# EscapeRoom_Shield_Mega_Master.net
KiCad netlist of a schematic drawn in EAGLE
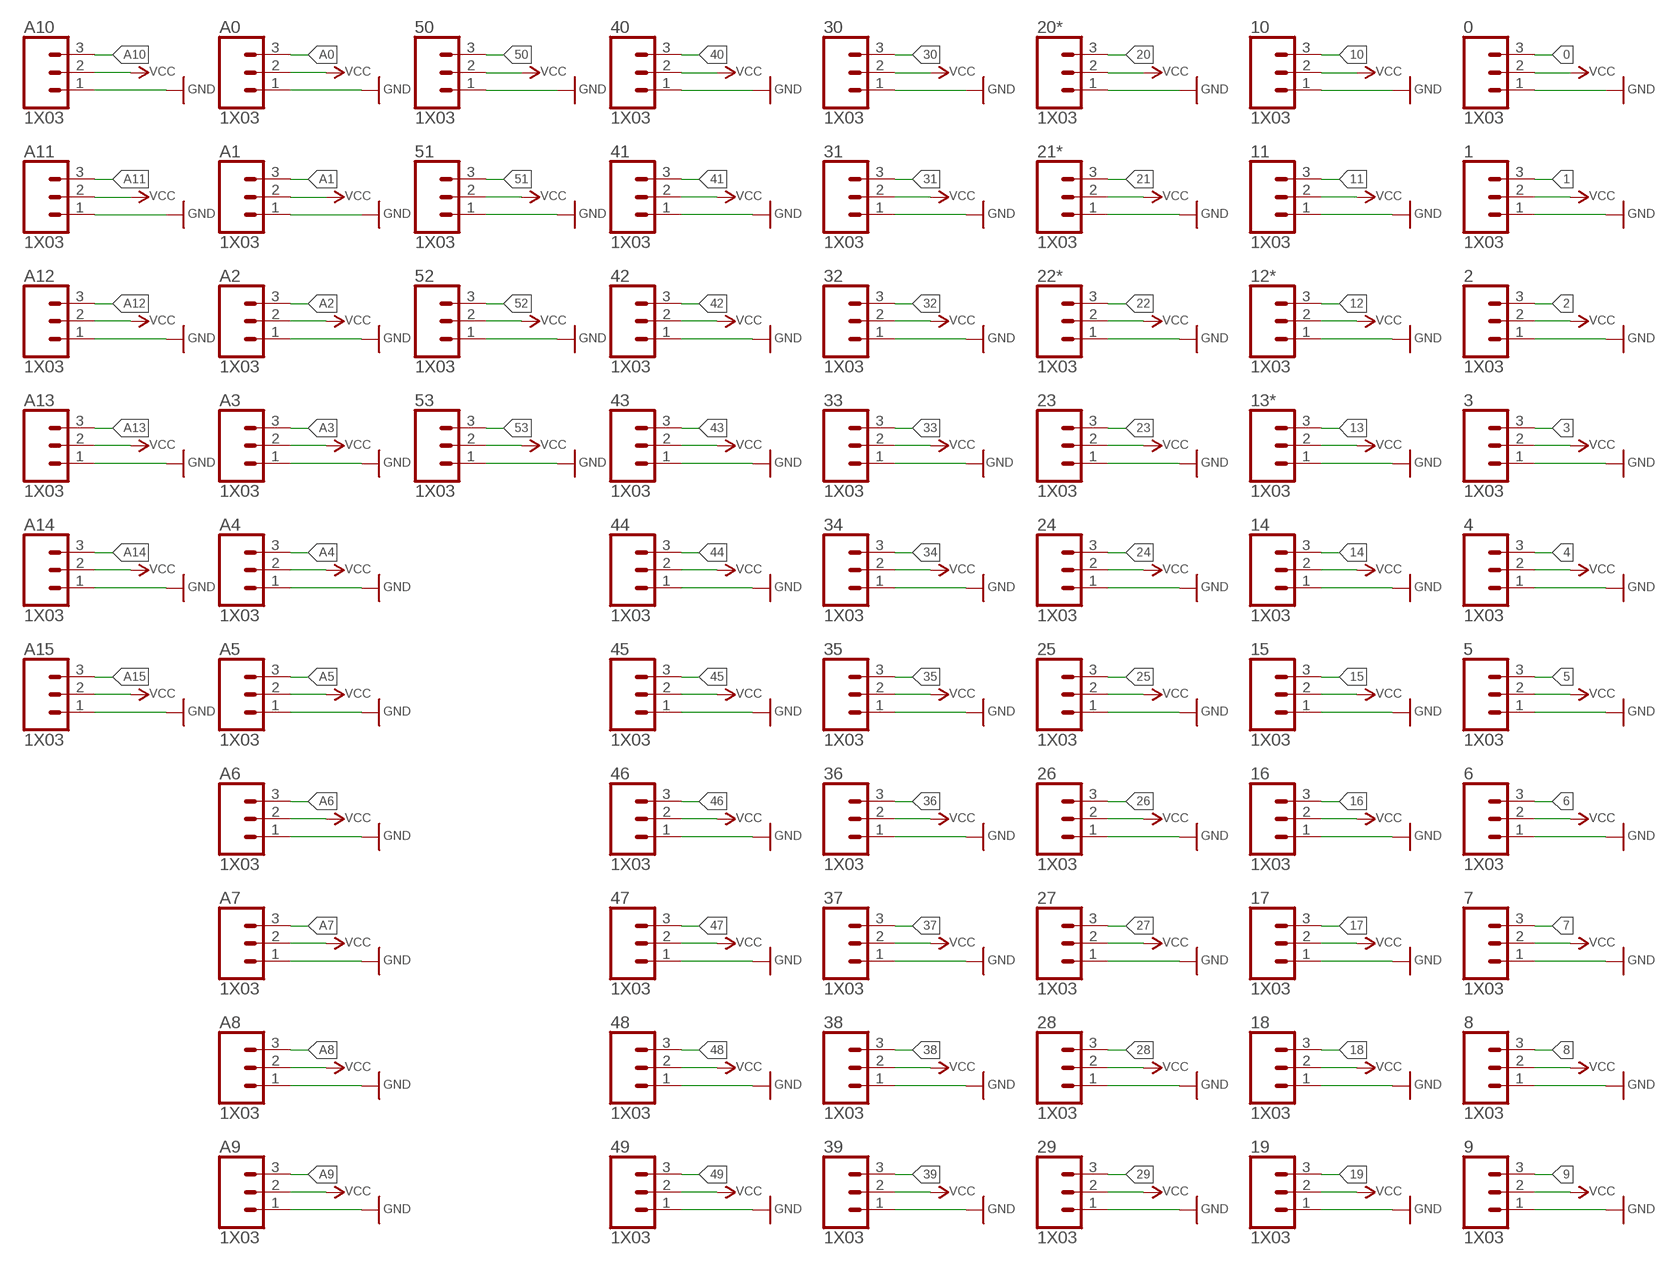
[diagram p0: schematic, sheet 1, part 1 of 2]
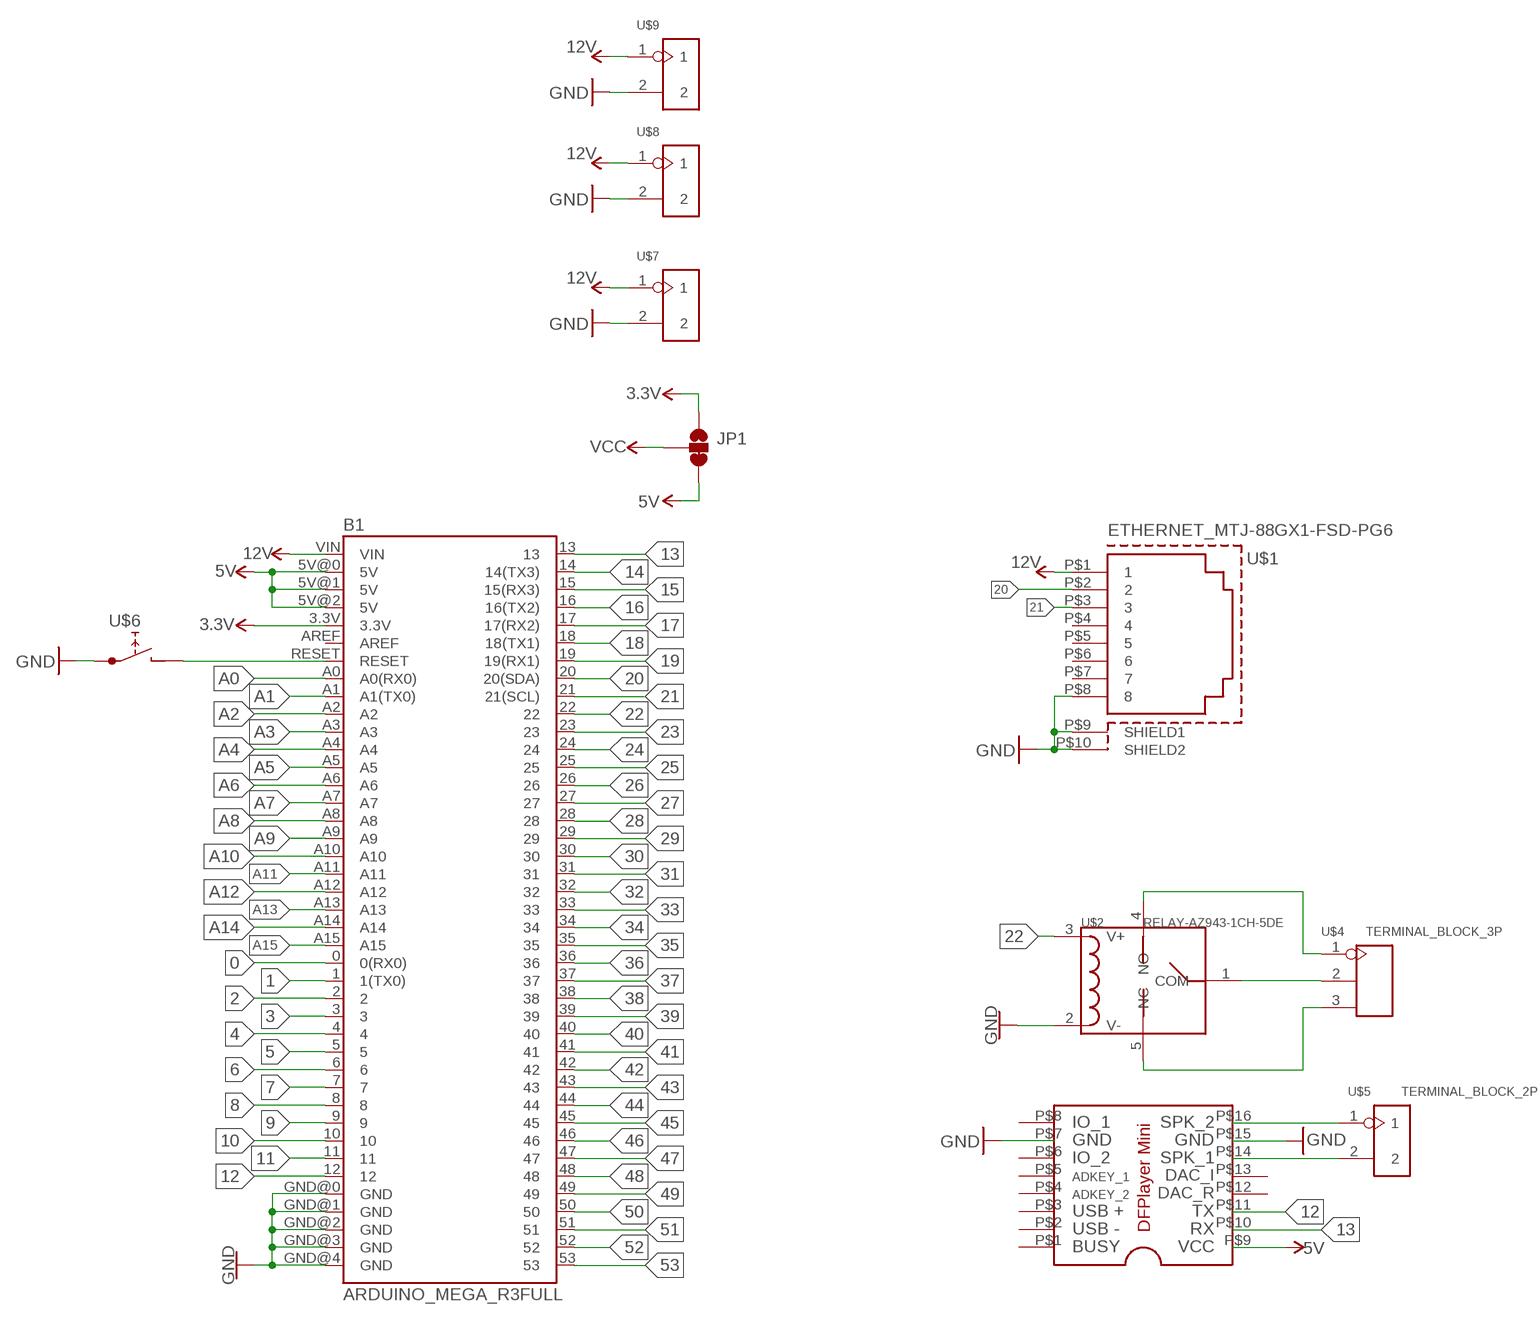
[diagram p1: schematic, sheet 1, part 2 of 2]

(export (version "E")
  (design (tool "Eeschema 10.0.6"))
  (components
    (comp (ref "0")
      (value "1X03")
      (footprint "eagle-import:1X03")
      (libsource (lib "eagle-import") (part "1X03"))
    )
    (comp (ref "1")
      (value "1X03")
      (footprint "eagle-import:1X03")
      (libsource (lib "eagle-import") (part "1X03"))
    )
    (comp (ref "2")
      (value "1X03")
      (footprint "eagle-import:1X03")
      (libsource (lib "eagle-import") (part "1X03"))
    )
    (comp (ref "3")
      (value "1X03")
      (footprint "eagle-import:1X03")
      (libsource (lib "eagle-import") (part "1X03"))
    )
    (comp (ref "4")
      (value "1X03")
      (footprint "eagle-import:1X03")
      (libsource (lib "eagle-import") (part "1X03"))
    )
    (comp (ref "5")
      (value "1X03")
      (footprint "eagle-import:1X03")
      (libsource (lib "eagle-import") (part "1X03"))
    )
    (comp (ref "6")
      (value "1X03")
      (footprint "eagle-import:1X03")
      (libsource (lib "eagle-import") (part "1X03"))
    )
    (comp (ref "7")
      (value "1X03")
      (footprint "eagle-import:1X03")
      (libsource (lib "eagle-import") (part "1X03"))
    )
    (comp (ref "8")
      (value "1X03")
      (footprint "eagle-import:1X03")
      (libsource (lib "eagle-import") (part "1X03"))
    )
    (comp (ref "9")
      (value "1X03")
      (footprint "eagle-import:1X03")
      (libsource (lib "eagle-import") (part "1X03"))
    )
    (comp (ref "10")
      (value "1X03")
      (footprint "eagle-import:1X03")
      (libsource (lib "eagle-import") (part "1X03"))
    )
    (comp (ref "11")
      (value "1X03")
      (footprint "eagle-import:1X03")
      (libsource (lib "eagle-import") (part "1X03"))
    )
    (comp (ref "12*")
      (value "1X03")
      (footprint "eagle-import:1X03")
      (libsource (lib "eagle-import") (part "1X03"))
    )
    (comp (ref "13*")
      (value "1X03")
      (footprint "eagle-import:1X03")
      (libsource (lib "eagle-import") (part "1X03"))
    )
    (comp (ref "14")
      (value "1X03")
      (footprint "eagle-import:1X03")
      (libsource (lib "eagle-import") (part "1X03"))
    )
    (comp (ref "15")
      (value "1X03")
      (footprint "eagle-import:1X03")
      (libsource (lib "eagle-import") (part "1X03"))
    )
    (comp (ref "16")
      (value "1X03")
      (footprint "eagle-import:1X03")
      (libsource (lib "eagle-import") (part "1X03"))
    )
    (comp (ref "17")
      (value "1X03")
      (footprint "eagle-import:1X03")
      (libsource (lib "eagle-import") (part "1X03"))
    )
    (comp (ref "18")
      (value "1X03")
      (footprint "eagle-import:1X03")
      (libsource (lib "eagle-import") (part "1X03"))
    )
    (comp (ref "19")
      (value "1X03")
      (footprint "eagle-import:1X03")
      (libsource (lib "eagle-import") (part "1X03"))
    )
    (comp (ref "20*")
      (value "1X03")
      (footprint "eagle-import:1X03")
      (libsource (lib "eagle-import") (part "1X03"))
    )
    (comp (ref "21*")
      (value "1X03")
      (footprint "eagle-import:1X03")
      (libsource (lib "eagle-import") (part "1X03"))
    )
    (comp (ref "22*")
      (value "1X03")
      (footprint "eagle-import:1X03")
      (libsource (lib "eagle-import") (part "1X03"))
    )
    (comp (ref "23")
      (value "1X03")
      (footprint "eagle-import:1X03")
      (libsource (lib "eagle-import") (part "1X03"))
    )
    (comp (ref "24")
      (value "1X03")
      (footprint "eagle-import:1X03")
      (libsource (lib "eagle-import") (part "1X03"))
    )
    (comp (ref "25")
      (value "1X03")
      (footprint "eagle-import:1X03")
      (libsource (lib "eagle-import") (part "1X03"))
    )
    (comp (ref "26")
      (value "1X03")
      (footprint "eagle-import:1X03")
      (libsource (lib "eagle-import") (part "1X03"))
    )
    (comp (ref "27")
      (value "1X03")
      (footprint "eagle-import:1X03")
      (libsource (lib "eagle-import") (part "1X03"))
    )
    (comp (ref "28")
      (value "1X03")
      (footprint "eagle-import:1X03")
      (libsource (lib "eagle-import") (part "1X03"))
    )
    (comp (ref "29")
      (value "1X03")
      (footprint "eagle-import:1X03")
      (libsource (lib "eagle-import") (part "1X03"))
    )
    (comp (ref "30")
      (value "1X03")
      (footprint "eagle-import:1X03")
      (libsource (lib "eagle-import") (part "1X03"))
    )
    (comp (ref "31")
      (value "1X03")
      (footprint "eagle-import:1X03")
      (libsource (lib "eagle-import") (part "1X03"))
    )
    (comp (ref "32")
      (value "1X03")
      (footprint "eagle-import:1X03")
      (libsource (lib "eagle-import") (part "1X03"))
    )
    (comp (ref "33")
      (value "1X03")
      (footprint "eagle-import:1X03")
      (libsource (lib "eagle-import") (part "1X03"))
    )
    (comp (ref "34")
      (value "1X03")
      (footprint "eagle-import:1X03")
      (libsource (lib "eagle-import") (part "1X03"))
    )
    (comp (ref "35")
      (value "1X03")
      (footprint "eagle-import:1X03")
      (libsource (lib "eagle-import") (part "1X03"))
    )
    (comp (ref "36")
      (value "1X03")
      (footprint "eagle-import:1X03")
      (libsource (lib "eagle-import") (part "1X03"))
    )
    (comp (ref "37")
      (value "1X03")
      (footprint "eagle-import:1X03")
      (libsource (lib "eagle-import") (part "1X03"))
    )
    (comp (ref "38")
      (value "1X03")
      (footprint "eagle-import:1X03")
      (libsource (lib "eagle-import") (part "1X03"))
    )
    (comp (ref "39")
      (value "1X03")
      (footprint "eagle-import:1X03")
      (libsource (lib "eagle-import") (part "1X03"))
    )
    (comp (ref "40")
      (value "1X03")
      (footprint "eagle-import:1X03")
      (libsource (lib "eagle-import") (part "1X03"))
    )
    (comp (ref "41")
      (value "1X03")
      (footprint "eagle-import:1X03")
      (libsource (lib "eagle-import") (part "1X03"))
    )
    (comp (ref "42")
      (value "1X03")
      (footprint "eagle-import:1X03")
      (libsource (lib "eagle-import") (part "1X03"))
    )
    (comp (ref "43")
      (value "1X03")
      (footprint "eagle-import:1X03")
      (libsource (lib "eagle-import") (part "1X03"))
    )
    (comp (ref "44")
      (value "1X03")
      (footprint "eagle-import:1X03")
      (libsource (lib "eagle-import") (part "1X03"))
    )
    (comp (ref "45")
      (value "1X03")
      (footprint "eagle-import:1X03")
      (libsource (lib "eagle-import") (part "1X03"))
    )
    (comp (ref "46")
      (value "1X03")
      (footprint "eagle-import:1X03")
      (libsource (lib "eagle-import") (part "1X03"))
    )
    (comp (ref "47")
      (value "1X03")
      (footprint "eagle-import:1X03")
      (libsource (lib "eagle-import") (part "1X03"))
    )
    (comp (ref "48")
      (value "1X03")
      (footprint "eagle-import:1X03")
      (libsource (lib "eagle-import") (part "1X03"))
    )
    (comp (ref "49")
      (value "1X03")
      (footprint "eagle-import:1X03")
      (libsource (lib "eagle-import") (part "1X03"))
    )
    (comp (ref "50")
      (value "1X03")
      (footprint "eagle-import:1X03")
      (libsource (lib "eagle-import") (part "1X03"))
    )
    (comp (ref "51")
      (value "1X03")
      (footprint "eagle-import:1X03")
      (libsource (lib "eagle-import") (part "1X03"))
    )
    (comp (ref "52")
      (value "1X03")
      (footprint "eagle-import:1X03")
      (libsource (lib "eagle-import") (part "1X03"))
    )
    (comp (ref "53")
      (value "1X03")
      (footprint "eagle-import:1X03")
      (libsource (lib "eagle-import") (part "1X03"))
    )
    (comp (ref "A0")
      (value "1X03")
      (footprint "eagle-import:1X03")
      (libsource (lib "eagle-import") (part "1X03"))
    )
    (comp (ref "A1")
      (value "1X03")
      (footprint "eagle-import:1X03")
      (libsource (lib "eagle-import") (part "1X03"))
    )
    (comp (ref "A2")
      (value "1X03")
      (footprint "eagle-import:1X03")
      (libsource (lib "eagle-import") (part "1X03"))
    )
    (comp (ref "A3")
      (value "1X03")
      (footprint "eagle-import:1X03")
      (libsource (lib "eagle-import") (part "1X03"))
    )
    (comp (ref "A4")
      (value "1X03")
      (footprint "eagle-import:1X03")
      (libsource (lib "eagle-import") (part "1X03"))
    )
    (comp (ref "A5")
      (value "1X03")
      (footprint "eagle-import:1X03")
      (libsource (lib "eagle-import") (part "1X03"))
    )
    (comp (ref "A6")
      (value "1X03")
      (footprint "eagle-import:1X03")
      (libsource (lib "eagle-import") (part "1X03"))
    )
    (comp (ref "A7")
      (value "1X03")
      (footprint "eagle-import:1X03")
      (libsource (lib "eagle-import") (part "1X03"))
    )
    (comp (ref "A8")
      (value "1X03")
      (footprint "eagle-import:1X03")
      (libsource (lib "eagle-import") (part "1X03"))
    )
    (comp (ref "A9")
      (value "1X03")
      (footprint "eagle-import:1X03")
      (libsource (lib "eagle-import") (part "1X03"))
    )
    (comp (ref "A10")
      (value "1X03")
      (footprint "eagle-import:1X03")
      (libsource (lib "eagle-import") (part "1X03"))
    )
    (comp (ref "A11")
      (value "1X03")
      (footprint "eagle-import:1X03")
      (libsource (lib "eagle-import") (part "1X03"))
    )
    (comp (ref "A12")
      (value "1X03")
      (footprint "eagle-import:1X03")
      (libsource (lib "eagle-import") (part "1X03"))
    )
    (comp (ref "A13")
      (value "1X03")
      (footprint "eagle-import:1X03")
      (libsource (lib "eagle-import") (part "1X03"))
    )
    (comp (ref "A14")
      (value "1X03")
      (footprint "eagle-import:1X03")
      (libsource (lib "eagle-import") (part "1X03"))
    )
    (comp (ref "A15")
      (value "1X03")
      (footprint "eagle-import:1X03")
      (libsource (lib "eagle-import") (part "1X03"))
    )
    (comp (ref "B1")
      (value "ARDUINO_MEGA_R3FULL")
      (footprint "eagle-import:ARDUINO_MEGA")
      (libsource (lib "eagle-import") (part "ARDUINO_MEGA_R3FULL"))
    )
    (comp (ref "JP1")
      (value "JUMPER-SMT_3_1-NC_TRACE_SILK")
      (footprint "eagle-import:SMT-JUMPER_3_1-NC_TRACE_SILK")
      (libsource (lib "eagle-import") (part "JUMPER-SMT_3_1-NC_TRACE_SILK"))
    )
    (comp (ref "U$1")
      (value "ETHERNET_MTJ-88GX1-FSD-PG6")
      (footprint "eagle-import:RJ45_MTJ-88GX1-FSD-PG6")
      (libsource (lib "eagle-import") (part "ETHERNET_MTJ-88GX1-FSD-PG6"))
    )
    (comp (ref "U$2")
      (value "RELAY-AZ943-1CH-5DE")
      (footprint "eagle-import:RELAY-19.0X15.0X15.0MM")
      (libsource (lib "eagle-import") (part "RELAY-AZ943-1CH-5DE"))
    )
    (comp (ref "U$3")
      (value "DFPLAYER_MINI")
      (footprint "eagle-import:DFMINI")
      (libsource (lib "eagle-import") (part "DFPLAYER_MINI"))
    )
    (comp (ref "U$4")
      (value "TERMINAL_BLOCK_3P")
      (footprint "eagle-import:H3-5.0-15.5X8.0MM")
      (libsource (lib "eagle-import") (part "TERMINAL_BLOCK_3P"))
    )
    (comp (ref "U$5")
      (value "TERMINAL_BLOCK_2P")
      (footprint "eagle-import:H2-5.0-10.5X8.0MM")
      (libsource (lib "eagle-import") (part "TERMINAL_BLOCK_2P"))
    )
    (comp (ref "U$6")
      (value "BUTTON_PTS636_SL50_LFS")
      (footprint "eagle-import:BUTTON_PTS636_SL50_LFS")
      (libsource (lib "eagle-import") (part "BUTTON_PTS636_SL50_LFS"))
    )
    (comp (ref "U$7")
      (value "TERMINAL_BLOCK_2P")
      (footprint "eagle-import:H2-5.0-10.5X8.0MM")
      (libsource (lib "eagle-import") (part "TERMINAL_BLOCK_2P"))
    )
    (comp (ref "U$8")
      (value "TERMINAL_BLOCK_2P")
      (footprint "eagle-import:H2-5.0-10.5X8.0MM")
      (libsource (lib "eagle-import") (part "TERMINAL_BLOCK_2P"))
    )
    (comp (ref "U$9")
      (value "TERMINAL_BLOCK_2P")
      (footprint "eagle-import:H2-5.0-10.5X8.0MM")
      (libsource (lib "eagle-import") (part "TERMINAL_BLOCK_2P"))
    )
  )
  (nets
    (net (code "1") (name "0") (class "Default")
      (node (ref "0") (pin "3") (pinfunction "3_3") (pintype "passive"))
      (node (ref "B1") (pin "0") (pinfunction "0(RX0)_0") (pintype "bidirectional"))
    )
    (net (code "2") (name "1") (class "Default")
      (node (ref "1") (pin "3") (pinfunction "3_3") (pintype "passive"))
      (node (ref "B1") (pin "1") (pinfunction "1(TX0)_1") (pintype "bidirectional"))
    )
    (net (code "3") (name "2") (class "Default")
      (node (ref "2") (pin "3") (pinfunction "3_3") (pintype "passive"))
      (node (ref "B1") (pin "2") (pinfunction "2_2") (pintype "bidirectional"))
    )
    (net (code "4") (name "3") (class "Default")
      (node (ref "3") (pin "3") (pinfunction "3_3") (pintype "passive"))
      (node (ref "B1") (pin "3") (pinfunction "3_3") (pintype "bidirectional"))
    )
    (net (code "5") (name "3.3V") (class "Default")
      (node (ref "B1") (pin "3.3V") (pinfunction "3.3V_3.3V") (pintype "bidirectional"))
      (node (ref "JP1") (pin "1") (pinfunction "1_1") (pintype "passive"))
    )
    (net (code "6") (name "4") (class "Default")
      (node (ref "4") (pin "3") (pinfunction "3_3") (pintype "passive"))
      (node (ref "B1") (pin "4") (pinfunction "4_4") (pintype "bidirectional"))
    )
    (net (code "7") (name "5") (class "Default")
      (node (ref "5") (pin "3") (pinfunction "3_3") (pintype "passive"))
      (node (ref "B1") (pin "5") (pinfunction "5_5") (pintype "bidirectional"))
    )
    (net (code "8") (name "5V") (class "Default")
      (node (ref "B1") (pin "5V@0") (pinfunction "5V_5V@0") (pintype "bidirectional"))
      (node (ref "B1") (pin "5V@1") (pinfunction "5V_5V@1") (pintype "bidirectional"))
      (node (ref "B1") (pin "5V@2") (pinfunction "5V_5V@2") (pintype "bidirectional"))
      (node (ref "JP1") (pin "3") (pinfunction "3_3") (pintype "passive"))
      (node (ref "U$3") (pin "P$9") (pinfunction "P$9_P$9") (pintype "bidirectional"))
    )
    (net (code "9") (name "6") (class "Default")
      (node (ref "6") (pin "3") (pinfunction "3_3") (pintype "passive"))
      (node (ref "B1") (pin "6") (pinfunction "6_6") (pintype "bidirectional"))
    )
    (net (code "10") (name "7") (class "Default")
      (node (ref "7") (pin "3") (pinfunction "3_3") (pintype "passive"))
      (node (ref "B1") (pin "7") (pinfunction "7_7") (pintype "bidirectional"))
    )
    (net (code "11") (name "8") (class "Default")
      (node (ref "8") (pin "3") (pinfunction "3_3") (pintype "passive"))
      (node (ref "B1") (pin "8") (pinfunction "8_8") (pintype "bidirectional"))
    )
    (net (code "12") (name "9") (class "Default")
      (node (ref "9") (pin "3") (pinfunction "3_3") (pintype "passive"))
      (node (ref "B1") (pin "9") (pinfunction "9_9") (pintype "bidirectional"))
    )
    (net (code "13") (name "10") (class "Default")
      (node (ref "10") (pin "3") (pinfunction "3_3") (pintype "passive"))
      (node (ref "B1") (pin "10") (pinfunction "10_10") (pintype "bidirectional"))
    )
    (net (code "14") (name "11") (class "Default")
      (node (ref "11") (pin "3") (pinfunction "3_3") (pintype "passive"))
      (node (ref "B1") (pin "11") (pinfunction "11_11") (pintype "bidirectional"))
    )
    (net (code "15") (name "12") (class "Default")
      (node (ref "12*") (pin "3") (pinfunction "3_3") (pintype "passive"))
      (node (ref "B1") (pin "12") (pinfunction "12_12") (pintype "bidirectional"))
      (node (ref "U$3") (pin "P$11") (pinfunction "P$11_P$11") (pintype "bidirectional"))
    )
    (net (code "16") (name "12V") (class "Default")
      (node (ref "B1") (pin "VIN") (pinfunction "VIN_VIN") (pintype "bidirectional"))
      (node (ref "U$1") (pin "P$1") (pinfunction "1_P$1") (pintype "passive"))
      (node (ref "U$7") (pin "1") (pinfunction "1_1") (pintype "bidirectional"))
      (node (ref "U$8") (pin "1") (pinfunction "1_1") (pintype "bidirectional"))
      (node (ref "U$9") (pin "1") (pinfunction "1_1") (pintype "bidirectional"))
    )
    (net (code "17") (name "13") (class "Default")
      (node (ref "13*") (pin "3") (pinfunction "3_3") (pintype "passive"))
      (node (ref "B1") (pin "13") (pinfunction "13_13") (pintype "bidirectional"))
      (node (ref "U$3") (pin "P$10") (pinfunction "P$10_P$10") (pintype "bidirectional"))
    )
    (net (code "18") (name "14") (class "Default")
      (node (ref "14") (pin "3") (pinfunction "3_3") (pintype "passive"))
      (node (ref "B1") (pin "14") (pinfunction "14(TX3)_14") (pintype "bidirectional"))
    )
    (net (code "19") (name "15") (class "Default")
      (node (ref "15") (pin "3") (pinfunction "3_3") (pintype "passive"))
      (node (ref "B1") (pin "15") (pinfunction "15(RX3)_15") (pintype "bidirectional"))
    )
    (net (code "20") (name "16") (class "Default")
      (node (ref "16") (pin "3") (pinfunction "3_3") (pintype "passive"))
      (node (ref "B1") (pin "16") (pinfunction "16(TX2)_16") (pintype "bidirectional"))
    )
    (net (code "21") (name "17") (class "Default")
      (node (ref "17") (pin "3") (pinfunction "3_3") (pintype "passive"))
      (node (ref "B1") (pin "17") (pinfunction "17(RX2)_17") (pintype "bidirectional"))
    )
    (net (code "22") (name "18") (class "Default")
      (node (ref "18") (pin "3") (pinfunction "3_3") (pintype "passive"))
      (node (ref "B1") (pin "18") (pinfunction "18(TX1)_18") (pintype "bidirectional"))
    )
    (net (code "23") (name "19") (class "Default")
      (node (ref "19") (pin "3") (pinfunction "3_3") (pintype "passive"))
      (node (ref "B1") (pin "19") (pinfunction "19(RX1)_19") (pintype "bidirectional"))
    )
    (net (code "24") (name "20") (class "Default")
      (node (ref "20*") (pin "3") (pinfunction "3_3") (pintype "passive"))
      (node (ref "B1") (pin "20") (pinfunction "20(SDA)_20") (pintype "bidirectional"))
      (node (ref "U$1") (pin "P$2") (pinfunction "2_P$2") (pintype "passive"))
    )
    (net (code "25") (name "21") (class "Default")
      (node (ref "21*") (pin "3") (pinfunction "3_3") (pintype "passive"))
      (node (ref "B1") (pin "21") (pinfunction "21(SCL)_21") (pintype "bidirectional"))
      (node (ref "U$1") (pin "P$3") (pinfunction "3_P$3") (pintype "passive"))
    )
    (net (code "26") (name "22") (class "Default")
      (node (ref "22*") (pin "3") (pinfunction "3_3") (pintype "passive"))
      (node (ref "B1") (pin "22") (pinfunction "22_22") (pintype "bidirectional"))
      (node (ref "U$2") (pin "3") (pinfunction "V+_3") (pintype "bidirectional"))
    )
    (net (code "27") (name "23") (class "Default")
      (node (ref "23") (pin "3") (pinfunction "3_3") (pintype "passive"))
      (node (ref "B1") (pin "23") (pinfunction "23_23") (pintype "bidirectional"))
    )
    (net (code "28") (name "24") (class "Default")
      (node (ref "24") (pin "3") (pinfunction "3_3") (pintype "passive"))
      (node (ref "B1") (pin "24") (pinfunction "24_24") (pintype "bidirectional"))
    )
    (net (code "29") (name "25") (class "Default")
      (node (ref "25") (pin "3") (pinfunction "3_3") (pintype "passive"))
      (node (ref "B1") (pin "25") (pinfunction "25_25") (pintype "bidirectional"))
    )
    (net (code "30") (name "26") (class "Default")
      (node (ref "26") (pin "3") (pinfunction "3_3") (pintype "passive"))
      (node (ref "B1") (pin "26") (pinfunction "26_26") (pintype "bidirectional"))
    )
    (net (code "31") (name "27") (class "Default")
      (node (ref "27") (pin "3") (pinfunction "3_3") (pintype "passive"))
      (node (ref "B1") (pin "27") (pinfunction "27_27") (pintype "bidirectional"))
    )
    (net (code "32") (name "28") (class "Default")
      (node (ref "28") (pin "3") (pinfunction "3_3") (pintype "passive"))
      (node (ref "B1") (pin "28") (pinfunction "28_28") (pintype "bidirectional"))
    )
    (net (code "33") (name "29") (class "Default")
      (node (ref "29") (pin "3") (pinfunction "3_3") (pintype "passive"))
      (node (ref "B1") (pin "29") (pinfunction "29_29") (pintype "bidirectional"))
    )
    (net (code "34") (name "30") (class "Default")
      (node (ref "30") (pin "3") (pinfunction "3_3") (pintype "passive"))
      (node (ref "B1") (pin "30") (pinfunction "30_30") (pintype "bidirectional"))
    )
    (net (code "35") (name "31") (class "Default")
      (node (ref "31") (pin "3") (pinfunction "3_3") (pintype "passive"))
      (node (ref "B1") (pin "31") (pinfunction "31_31") (pintype "bidirectional"))
    )
    (net (code "36") (name "32") (class "Default")
      (node (ref "32") (pin "3") (pinfunction "3_3") (pintype "passive"))
      (node (ref "B1") (pin "32") (pinfunction "32_32") (pintype "bidirectional"))
    )
    (net (code "37") (name "33") (class "Default")
      (node (ref "33") (pin "3") (pinfunction "3_3") (pintype "passive"))
      (node (ref "B1") (pin "33") (pinfunction "33_33") (pintype "bidirectional"))
    )
    (net (code "38") (name "34") (class "Default")
      (node (ref "34") (pin "3") (pinfunction "3_3") (pintype "passive"))
      (node (ref "B1") (pin "34") (pinfunction "34_34") (pintype "bidirectional"))
    )
    (net (code "39") (name "35") (class "Default")
      (node (ref "35") (pin "3") (pinfunction "3_3") (pintype "passive"))
      (node (ref "B1") (pin "35") (pinfunction "35_35") (pintype "bidirectional"))
    )
    (net (code "40") (name "36") (class "Default")
      (node (ref "36") (pin "3") (pinfunction "3_3") (pintype "passive"))
      (node (ref "B1") (pin "36") (pinfunction "36_36") (pintype "bidirectional"))
    )
    (net (code "41") (name "37") (class "Default")
      (node (ref "37") (pin "3") (pinfunction "3_3") (pintype "passive"))
      (node (ref "B1") (pin "37") (pinfunction "37_37") (pintype "bidirectional"))
    )
    (net (code "42") (name "38") (class "Default")
      (node (ref "38") (pin "3") (pinfunction "3_3") (pintype "passive"))
      (node (ref "B1") (pin "38") (pinfunction "38_38") (pintype "bidirectional"))
    )
    (net (code "43") (name "39") (class "Default")
      (node (ref "39") (pin "3") (pinfunction "3_3") (pintype "passive"))
      (node (ref "B1") (pin "39") (pinfunction "39_39") (pintype "bidirectional"))
    )
    (net (code "44") (name "40") (class "Default")
      (node (ref "40") (pin "3") (pinfunction "3_3") (pintype "passive"))
      (node (ref "B1") (pin "40") (pinfunction "40_40") (pintype "bidirectional"))
    )
    (net (code "45") (name "41") (class "Default")
      (node (ref "41") (pin "3") (pinfunction "3_3") (pintype "passive"))
      (node (ref "B1") (pin "41") (pinfunction "41_41") (pintype "bidirectional"))
    )
    (net (code "46") (name "42") (class "Default")
      (node (ref "42") (pin "3") (pinfunction "3_3") (pintype "passive"))
      (node (ref "B1") (pin "42") (pinfunction "42_42") (pintype "bidirectional"))
    )
    (net (code "47") (name "43") (class "Default")
      (node (ref "43") (pin "3") (pinfunction "3_3") (pintype "passive"))
      (node (ref "B1") (pin "43") (pinfunction "43_43") (pintype "bidirectional"))
    )
    (net (code "48") (name "44") (class "Default")
      (node (ref "44") (pin "3") (pinfunction "3_3") (pintype "passive"))
      (node (ref "B1") (pin "44") (pinfunction "44_44") (pintype "bidirectional"))
    )
    (net (code "49") (name "45") (class "Default")
      (node (ref "45") (pin "3") (pinfunction "3_3") (pintype "passive"))
      (node (ref "B1") (pin "45") (pinfunction "45_45") (pintype "bidirectional"))
    )
    (net (code "50") (name "46") (class "Default")
      (node (ref "46") (pin "3") (pinfunction "3_3") (pintype "passive"))
      (node (ref "B1") (pin "46") (pinfunction "46_46") (pintype "bidirectional"))
    )
    (net (code "51") (name "47") (class "Default")
      (node (ref "47") (pin "3") (pinfunction "3_3") (pintype "passive"))
      (node (ref "B1") (pin "47") (pinfunction "47_47") (pintype "bidirectional"))
    )
    (net (code "52") (name "48") (class "Default")
      (node (ref "48") (pin "3") (pinfunction "3_3") (pintype "passive"))
      (node (ref "B1") (pin "48") (pinfunction "48_48") (pintype "bidirectional"))
    )
    (net (code "53") (name "49") (class "Default")
      (node (ref "49") (pin "3") (pinfunction "3_3") (pintype "passive"))
      (node (ref "B1") (pin "49") (pinfunction "49_49") (pintype "bidirectional"))
    )
    (net (code "54") (name "50") (class "Default")
      (node (ref "50") (pin "3") (pinfunction "3_3") (pintype "passive"))
      (node (ref "B1") (pin "50") (pinfunction "50_50") (pintype "bidirectional"))
    )
    (net (code "55") (name "51") (class "Default")
      (node (ref "51") (pin "3") (pinfunction "3_3") (pintype "passive"))
      (node (ref "B1") (pin "51") (pinfunction "51_51") (pintype "bidirectional"))
    )
    (net (code "56") (name "52") (class "Default")
      (node (ref "52") (pin "3") (pinfunction "3_3") (pintype "passive"))
      (node (ref "B1") (pin "52") (pinfunction "52_52") (pintype "bidirectional"))
    )
    (net (code "57") (name "53") (class "Default")
      (node (ref "53") (pin "3") (pinfunction "3_3") (pintype "passive"))
      (node (ref "B1") (pin "53") (pinfunction "53_53") (pintype "bidirectional"))
    )
    (net (code "58") (name "A0") (class "Default")
      (node (ref "A0") (pin "3") (pinfunction "3_3") (pintype "passive"))
      (node (ref "B1") (pin "A0") (pinfunction "A0(RX0)_A0") (pintype "bidirectional"))
    )
    (net (code "59") (name "A1") (class "Default")
      (node (ref "A1") (pin "3") (pinfunction "3_3") (pintype "passive"))
      (node (ref "B1") (pin "A1") (pinfunction "A1(TX0)_A1") (pintype "bidirectional"))
    )
    (net (code "60") (name "A2") (class "Default")
      (node (ref "A2") (pin "3") (pinfunction "3_3") (pintype "passive"))
      (node (ref "B1") (pin "A2") (pinfunction "A2_A2") (pintype "bidirectional"))
    )
    (net (code "61") (name "A3") (class "Default")
      (node (ref "A3") (pin "3") (pinfunction "3_3") (pintype "passive"))
      (node (ref "B1") (pin "A3") (pinfunction "A3_A3") (pintype "bidirectional"))
    )
    (net (code "62") (name "A4") (class "Default")
      (node (ref "A4") (pin "3") (pinfunction "3_3") (pintype "passive"))
      (node (ref "B1") (pin "A4") (pinfunction "A4_A4") (pintype "bidirectional"))
    )
    (net (code "63") (name "A5") (class "Default")
      (node (ref "A5") (pin "3") (pinfunction "3_3") (pintype "passive"))
      (node (ref "B1") (pin "A5") (pinfunction "A5_A5") (pintype "bidirectional"))
    )
    (net (code "64") (name "A6") (class "Default")
      (node (ref "A6") (pin "3") (pinfunction "3_3") (pintype "passive"))
      (node (ref "B1") (pin "A6") (pinfunction "A6_A6") (pintype "bidirectional"))
    )
    (net (code "65") (name "A7") (class "Default")
      (node (ref "A7") (pin "3") (pinfunction "3_3") (pintype "passive"))
      (node (ref "B1") (pin "A7") (pinfunction "A7_A7") (pintype "bidirectional"))
    )
    (net (code "66") (name "A8") (class "Default")
      (node (ref "A8") (pin "3") (pinfunction "3_3") (pintype "passive"))
      (node (ref "B1") (pin "A8") (pinfunction "A8_A8") (pintype "bidirectional"))
    )
    (net (code "67") (name "A9") (class "Default")
      (node (ref "A9") (pin "3") (pinfunction "3_3") (pintype "passive"))
      (node (ref "B1") (pin "A9") (pinfunction "A9_A9") (pintype "bidirectional"))
    )
    (net (code "68") (name "A10") (class "Default")
      (node (ref "A10") (pin "3") (pinfunction "3_3") (pintype "passive"))
      (node (ref "B1") (pin "A10") (pinfunction "A10_A10") (pintype "bidirectional"))
    )
    (net (code "69") (name "A11") (class "Default")
      (node (ref "A11") (pin "3") (pinfunction "3_3") (pintype "passive"))
      (node (ref "B1") (pin "A11") (pinfunction "A11_A11") (pintype "bidirectional"))
    )
    (net (code "70") (name "A12") (class "Default")
      (node (ref "A12") (pin "3") (pinfunction "3_3") (pintype "passive"))
      (node (ref "B1") (pin "A12") (pinfunction "A12_A12") (pintype "bidirectional"))
    )
    (net (code "71") (name "A13") (class "Default")
      (node (ref "A13") (pin "3") (pinfunction "3_3") (pintype "passive"))
      (node (ref "B1") (pin "A13") (pinfunction "A13_A13") (pintype "bidirectional"))
    )
    (net (code "72") (name "A14") (class "Default")
      (node (ref "A14") (pin "3") (pinfunction "3_3") (pintype "passive"))
      (node (ref "B1") (pin "A14") (pinfunction "A14_A14") (pintype "bidirectional"))
    )
    (net (code "73") (name "A15") (class "Default")
      (node (ref "A15") (pin "3") (pinfunction "3_3") (pintype "passive"))
      (node (ref "B1") (pin "A15") (pinfunction "A15_A15") (pintype "bidirectional"))
    )
    (net (code "74") (name "GND") (class "Default")
      (node (ref "0") (pin "1") (pinfunction "1_1") (pintype "passive"))
      (node (ref "1") (pin "1") (pinfunction "1_1") (pintype "passive"))
      (node (ref "10") (pin "1") (pinfunction "1_1") (pintype "passive"))
      (node (ref "11") (pin "1") (pinfunction "1_1") (pintype "passive"))
      (node (ref "12*") (pin "1") (pinfunction "1_1") (pintype "passive"))
      (node (ref "13*") (pin "1") (pinfunction "1_1") (pintype "passive"))
      (node (ref "14") (pin "1") (pinfunction "1_1") (pintype "passive"))
      (node (ref "15") (pin "1") (pinfunction "1_1") (pintype "passive"))
      (node (ref "16") (pin "1") (pinfunction "1_1") (pintype "passive"))
      (node (ref "17") (pin "1") (pinfunction "1_1") (pintype "passive"))
      (node (ref "18") (pin "1") (pinfunction "1_1") (pintype "passive"))
      (node (ref "19") (pin "1") (pinfunction "1_1") (pintype "passive"))
      (node (ref "2") (pin "1") (pinfunction "1_1") (pintype "passive"))
      (node (ref "20*") (pin "1") (pinfunction "1_1") (pintype "passive"))
      (node (ref "21*") (pin "1") (pinfunction "1_1") (pintype "passive"))
      (node (ref "22*") (pin "1") (pinfunction "1_1") (pintype "passive"))
      (node (ref "23") (pin "1") (pinfunction "1_1") (pintype "passive"))
      (node (ref "24") (pin "1") (pinfunction "1_1") (pintype "passive"))
      (node (ref "25") (pin "1") (pinfunction "1_1") (pintype "passive"))
      (node (ref "26") (pin "1") (pinfunction "1_1") (pintype "passive"))
      (node (ref "27") (pin "1") (pinfunction "1_1") (pintype "passive"))
      (node (ref "28") (pin "1") (pinfunction "1_1") (pintype "passive"))
      (node (ref "29") (pin "1") (pinfunction "1_1") (pintype "passive"))
      (node (ref "3") (pin "1") (pinfunction "1_1") (pintype "passive"))
      (node (ref "30") (pin "1") (pinfunction "1_1") (pintype "passive"))
      (node (ref "31") (pin "1") (pinfunction "1_1") (pintype "passive"))
      (node (ref "32") (pin "1") (pinfunction "1_1") (pintype "passive"))
      (node (ref "33") (pin "1") (pinfunction "1_1") (pintype "passive"))
      (node (ref "34") (pin "1") (pinfunction "1_1") (pintype "passive"))
      (node (ref "35") (pin "1") (pinfunction "1_1") (pintype "passive"))
      (node (ref "36") (pin "1") (pinfunction "1_1") (pintype "passive"))
      (node (ref "37") (pin "1") (pinfunction "1_1") (pintype "passive"))
      (node (ref "38") (pin "1") (pinfunction "1_1") (pintype "passive"))
      (node (ref "39") (pin "1") (pinfunction "1_1") (pintype "passive"))
      (node (ref "4") (pin "1") (pinfunction "1_1") (pintype "passive"))
      (node (ref "40") (pin "1") (pinfunction "1_1") (pintype "passive"))
      (node (ref "41") (pin "1") (pinfunction "1_1") (pintype "passive"))
      (node (ref "42") (pin "1") (pinfunction "1_1") (pintype "passive"))
      (node (ref "43") (pin "1") (pinfunction "1_1") (pintype "passive"))
      (node (ref "44") (pin "1") (pinfunction "1_1") (pintype "passive"))
      (node (ref "45") (pin "1") (pinfunction "1_1") (pintype "passive"))
      (node (ref "46") (pin "1") (pinfunction "1_1") (pintype "passive"))
      (node (ref "47") (pin "1") (pinfunction "1_1") (pintype "passive"))
      (node (ref "48") (pin "1") (pinfunction "1_1") (pintype "passive"))
      (node (ref "49") (pin "1") (pinfunction "1_1") (pintype "passive"))
      (node (ref "5") (pin "1") (pinfunction "1_1") (pintype "passive"))
      (node (ref "50") (pin "1") (pinfunction "1_1") (pintype "passive"))
      (node (ref "51") (pin "1") (pinfunction "1_1") (pintype "passive"))
      (node (ref "52") (pin "1") (pinfunction "1_1") (pintype "passive"))
      (node (ref "53") (pin "1") (pinfunction "1_1") (pintype "passive"))
      (node (ref "6") (pin "1") (pinfunction "1_1") (pintype "passive"))
      (node (ref "7") (pin "1") (pinfunction "1_1") (pintype "passive"))
      (node (ref "8") (pin "1") (pinfunction "1_1") (pintype "passive"))
      (node (ref "9") (pin "1") (pinfunction "1_1") (pintype "passive"))
      (node (ref "A0") (pin "1") (pinfunction "1_1") (pintype "passive"))
      (node (ref "A1") (pin "1") (pinfunction "1_1") (pintype "passive"))
      (node (ref "A10") (pin "1") (pinfunction "1_1") (pintype "passive"))
      (node (ref "A11") (pin "1") (pinfunction "1_1") (pintype "passive"))
      (node (ref "A12") (pin "1") (pinfunction "1_1") (pintype "passive"))
      (node (ref "A13") (pin "1") (pinfunction "1_1") (pintype "passive"))
      (node (ref "A14") (pin "1") (pinfunction "1_1") (pintype "passive"))
      (node (ref "A15") (pin "1") (pinfunction "1_1") (pintype "passive"))
      (node (ref "A2") (pin "1") (pinfunction "1_1") (pintype "passive"))
      (node (ref "A3") (pin "1") (pinfunction "1_1") (pintype "passive"))
      (node (ref "A4") (pin "1") (pinfunction "1_1") (pintype "passive"))
      (node (ref "A5") (pin "1") (pinfunction "1_1") (pintype "passive"))
      (node (ref "A6") (pin "1") (pinfunction "1_1") (pintype "passive"))
      (node (ref "A7") (pin "1") (pinfunction "1_1") (pintype "passive"))
      (node (ref "A8") (pin "1") (pinfunction "1_1") (pintype "passive"))
      (node (ref "A9") (pin "1") (pinfunction "1_1") (pintype "passive"))
      (node (ref "B1") (pin "GND@0") (pinfunction "GND_GND@0") (pintype "bidirectional"))
      (node (ref "B1") (pin "GND@1") (pinfunction "GND_GND@1") (pintype "bidirectional"))
      (node (ref "B1") (pin "GND@2") (pinfunction "GND_GND@2") (pintype "bidirectional"))
      (node (ref "B1") (pin "GND@3") (pinfunction "GND_GND@3") (pintype "bidirectional"))
      (node (ref "B1") (pin "GND@4") (pinfunction "GND_GND@4") (pintype "bidirectional"))
      (node (ref "U$1") (pin "P$10") (pinfunction "SHIELD2_P$10") (pintype "passive"))
      (node (ref "U$1") (pin "P$8") (pinfunction "8_P$8") (pintype "passive"))
      (node (ref "U$1") (pin "P$9") (pinfunction "SHIELD1_P$9") (pintype "passive"))
      (node (ref "U$2") (pin "2") (pinfunction "V-_2") (pintype "bidirectional"))
      (node (ref "U$3") (pin "P$15") (pinfunction "P$15_P$15") (pintype "bidirectional"))
      (node (ref "U$3") (pin "P$7") (pinfunction "P$7_P$7") (pintype "bidirectional"))
      (node (ref "U$6") (pin "P$1") (pinfunction "A1_P$1") (pintype "passive"))
      (node (ref "U$7") (pin "2") (pinfunction "2_2") (pintype "bidirectional"))
      (node (ref "U$8") (pin "2") (pinfunction "2_2") (pintype "bidirectional"))
      (node (ref "U$9") (pin "2") (pinfunction "2_2") (pintype "bidirectional"))
    )
    (net (code "75") (name "Net-(U$2-COM)") (class "Default")
      (node (ref "U$2") (pin "1") (pinfunction "COM_1") (pintype "bidirectional"))
      (node (ref "U$4") (pin "2") (pinfunction "P$2_2") (pintype "bidirectional"))
    )
    (net (code "76") (name "Net-(U$2-NC)") (class "Default")
      (node (ref "U$2") (pin "5") (pinfunction "NC_5") (pintype "bidirectional"))
      (node (ref "U$4") (pin "3") (pinfunction "P$3_3") (pintype "bidirectional"))
    )
    (net (code "77") (name "Net-(U$2-NO)") (class "Default")
      (node (ref "U$2") (pin "4") (pinfunction "NO_4") (pintype "bidirectional"))
      (node (ref "U$4") (pin "1") (pinfunction "P$1_1") (pintype "bidirectional"))
    )
    (net (code "78") (name "Net-(U$3-PadP$14)") (class "Default")
      (node (ref "U$3") (pin "P$14") (pinfunction "P$14_P$14") (pintype "bidirectional"))
      (node (ref "U$5") (pin "2") (pinfunction "2_2") (pintype "bidirectional"))
    )
    (net (code "79") (name "Net-(U$3-PadP$16)") (class "Default")
      (node (ref "U$3") (pin "P$16") (pinfunction "P$16_P$16") (pintype "bidirectional"))
      (node (ref "U$5") (pin "1") (pinfunction "1_1") (pintype "bidirectional"))
    )
    (net (code "80") (name "Net-(U$6-B)") (class "Default")
      (node (ref "B1") (pin "RESET") (pinfunction "RESET_RESET") (pintype "bidirectional"))
      (node (ref "U$6") (pin "P$2") (pinfunction "B_P$2") (pintype "passive"))
    )
    (net (code "81") (name "VCC") (class "Default")
      (node (ref "0") (pin "2") (pinfunction "2_2") (pintype "passive"))
      (node (ref "1") (pin "2") (pinfunction "2_2") (pintype "passive"))
      (node (ref "10") (pin "2") (pinfunction "2_2") (pintype "passive"))
      (node (ref "11") (pin "2") (pinfunction "2_2") (pintype "passive"))
      (node (ref "12*") (pin "2") (pinfunction "2_2") (pintype "passive"))
      (node (ref "13*") (pin "2") (pinfunction "2_2") (pintype "passive"))
      (node (ref "14") (pin "2") (pinfunction "2_2") (pintype "passive"))
      (node (ref "15") (pin "2") (pinfunction "2_2") (pintype "passive"))
      (node (ref "16") (pin "2") (pinfunction "2_2") (pintype "passive"))
      (node (ref "17") (pin "2") (pinfunction "2_2") (pintype "passive"))
      (node (ref "18") (pin "2") (pinfunction "2_2") (pintype "passive"))
      (node (ref "19") (pin "2") (pinfunction "2_2") (pintype "passive"))
      (node (ref "2") (pin "2") (pinfunction "2_2") (pintype "passive"))
      (node (ref "20*") (pin "2") (pinfunction "2_2") (pintype "passive"))
      (node (ref "21*") (pin "2") (pinfunction "2_2") (pintype "passive"))
      (node (ref "22*") (pin "2") (pinfunction "2_2") (pintype "passive"))
      (node (ref "23") (pin "2") (pinfunction "2_2") (pintype "passive"))
      (node (ref "24") (pin "2") (pinfunction "2_2") (pintype "passive"))
      (node (ref "25") (pin "2") (pinfunction "2_2") (pintype "passive"))
      (node (ref "26") (pin "2") (pinfunction "2_2") (pintype "passive"))
      (node (ref "27") (pin "2") (pinfunction "2_2") (pintype "passive"))
      (node (ref "28") (pin "2") (pinfunction "2_2") (pintype "passive"))
      (node (ref "29") (pin "2") (pinfunction "2_2") (pintype "passive"))
      (node (ref "3") (pin "2") (pinfunction "2_2") (pintype "passive"))
      (node (ref "30") (pin "2") (pinfunction "2_2") (pintype "passive"))
      (node (ref "31") (pin "2") (pinfunction "2_2") (pintype "passive"))
      (node (ref "32") (pin "2") (pinfunction "2_2") (pintype "passive"))
      (node (ref "33") (pin "2") (pinfunction "2_2") (pintype "passive"))
      (node (ref "34") (pin "2") (pinfunction "2_2") (pintype "passive"))
      (node (ref "35") (pin "2") (pinfunction "2_2") (pintype "passive"))
      (node (ref "36") (pin "2") (pinfunction "2_2") (pintype "passive"))
      (node (ref "37") (pin "2") (pinfunction "2_2") (pintype "passive"))
      (node (ref "38") (pin "2") (pinfunction "2_2") (pintype "passive"))
      (node (ref "39") (pin "2") (pinfunction "2_2") (pintype "passive"))
      (node (ref "4") (pin "2") (pinfunction "2_2") (pintype "passive"))
      (node (ref "40") (pin "2") (pinfunction "2_2") (pintype "passive"))
      (node (ref "41") (pin "2") (pinfunction "2_2") (pintype "passive"))
      (node (ref "42") (pin "2") (pinfunction "2_2") (pintype "passive"))
      (node (ref "43") (pin "2") (pinfunction "2_2") (pintype "passive"))
      (node (ref "44") (pin "2") (pinfunction "2_2") (pintype "passive"))
      (node (ref "45") (pin "2") (pinfunction "2_2") (pintype "passive"))
      (node (ref "46") (pin "2") (pinfunction "2_2") (pintype "passive"))
      (node (ref "47") (pin "2") (pinfunction "2_2") (pintype "passive"))
      (node (ref "48") (pin "2") (pinfunction "2_2") (pintype "passive"))
      (node (ref "49") (pin "2") (pinfunction "2_2") (pintype "passive"))
      (node (ref "5") (pin "2") (pinfunction "2_2") (pintype "passive"))
      (node (ref "50") (pin "2") (pinfunction "2_2") (pintype "passive"))
      (node (ref "51") (pin "2") (pinfunction "2_2") (pintype "passive"))
      (node (ref "52") (pin "2") (pinfunction "2_2") (pintype "passive"))
      (node (ref "53") (pin "2") (pinfunction "2_2") (pintype "passive"))
      (node (ref "6") (pin "2") (pinfunction "2_2") (pintype "passive"))
      (node (ref "7") (pin "2") (pinfunction "2_2") (pintype "passive"))
      (node (ref "8") (pin "2") (pinfunction "2_2") (pintype "passive"))
      (node (ref "9") (pin "2") (pinfunction "2_2") (pintype "passive"))
      (node (ref "A0") (pin "2") (pinfunction "2_2") (pintype "passive"))
      (node (ref "A1") (pin "2") (pinfunction "2_2") (pintype "passive"))
      (node (ref "A10") (pin "2") (pinfunction "2_2") (pintype "passive"))
      (node (ref "A11") (pin "2") (pinfunction "2_2") (pintype "passive"))
      (node (ref "A12") (pin "2") (pinfunction "2_2") (pintype "passive"))
      (node (ref "A13") (pin "2") (pinfunction "2_2") (pintype "passive"))
      (node (ref "A14") (pin "2") (pinfunction "2_2") (pintype "passive"))
      (node (ref "A15") (pin "2") (pinfunction "2_2") (pintype "passive"))
      (node (ref "A2") (pin "2") (pinfunction "2_2") (pintype "passive"))
      (node (ref "A3") (pin "2") (pinfunction "2_2") (pintype "passive"))
      (node (ref "A4") (pin "2") (pinfunction "2_2") (pintype "passive"))
      (node (ref "A5") (pin "2") (pinfunction "2_2") (pintype "passive"))
      (node (ref "A6") (pin "2") (pinfunction "2_2") (pintype "passive"))
      (node (ref "A7") (pin "2") (pinfunction "2_2") (pintype "passive"))
      (node (ref "A8") (pin "2") (pinfunction "2_2") (pintype "passive"))
      (node (ref "A9") (pin "2") (pinfunction "2_2") (pintype "passive"))
      (node (ref "JP1") (pin "2") (pinfunction "2_2") (pintype "passive"))
    )
    (net (code "82") (name "unconnected-(B1-PadAREF)") (class "Default")
      (node (ref "B1") (pin "AREF") (pinfunction "AREF_AREF") (pintype "bidirectional"))
    )
    (net (code "83") (name "unconnected-(U$1-4-PadP$4)") (class "Default")
      (node (ref "U$1") (pin "P$4") (pinfunction "4_P$4") (pintype "passive"))
    )
    (net (code "84") (name "unconnected-(U$1-5-PadP$5)") (class "Default")
      (node (ref "U$1") (pin "P$5") (pinfunction "5_P$5") (pintype "passive"))
    )
    (net (code "85") (name "unconnected-(U$1-6-PadP$6)") (class "Default")
      (node (ref "U$1") (pin "P$6") (pinfunction "6_P$6") (pintype "passive"))
    )
    (net (code "86") (name "unconnected-(U$1-7-PadP$7)") (class "Default")
      (node (ref "U$1") (pin "P$7") (pinfunction "7_P$7") (pintype "passive"))
    )
    (net (code "87") (name "unconnected-(U$3-PadP$1)") (class "Default")
      (node (ref "U$3") (pin "P$1") (pinfunction "P$1_P$1") (pintype "bidirectional"))
    )
    (net (code "88") (name "unconnected-(U$3-PadP$2)") (class "Default")
      (node (ref "U$3") (pin "P$2") (pinfunction "P$2_P$2") (pintype "bidirectional"))
    )
    (net (code "89") (name "unconnected-(U$3-PadP$3)") (class "Default")
      (node (ref "U$3") (pin "P$3") (pinfunction "P$3_P$3") (pintype "bidirectional"))
    )
    (net (code "90") (name "unconnected-(U$3-PadP$4)") (class "Default")
      (node (ref "U$3") (pin "P$4") (pinfunction "P$4_P$4") (pintype "bidirectional"))
    )
    (net (code "91") (name "unconnected-(U$3-PadP$5)") (class "Default")
      (node (ref "U$3") (pin "P$5") (pinfunction "P$5_P$5") (pintype "bidirectional"))
    )
    (net (code "92") (name "unconnected-(U$3-PadP$6)") (class "Default")
      (node (ref "U$3") (pin "P$6") (pinfunction "P$6_P$6") (pintype "bidirectional"))
    )
    (net (code "93") (name "unconnected-(U$3-PadP$8)") (class "Default")
      (node (ref "U$3") (pin "P$8") (pinfunction "P$8_P$8") (pintype "bidirectional"))
    )
    (net (code "94") (name "unconnected-(U$3-PadP$12)") (class "Default")
      (node (ref "U$3") (pin "P$12") (pinfunction "P$12_P$12") (pintype "bidirectional"))
    )
    (net (code "95") (name "unconnected-(U$3-PadP$13)") (class "Default")
      (node (ref "U$3") (pin "P$13") (pinfunction "P$13_P$13") (pintype "bidirectional"))
    )
  )
)
